# lcmeter.net
KiCad netlist of a schematic drawn in EAGLE
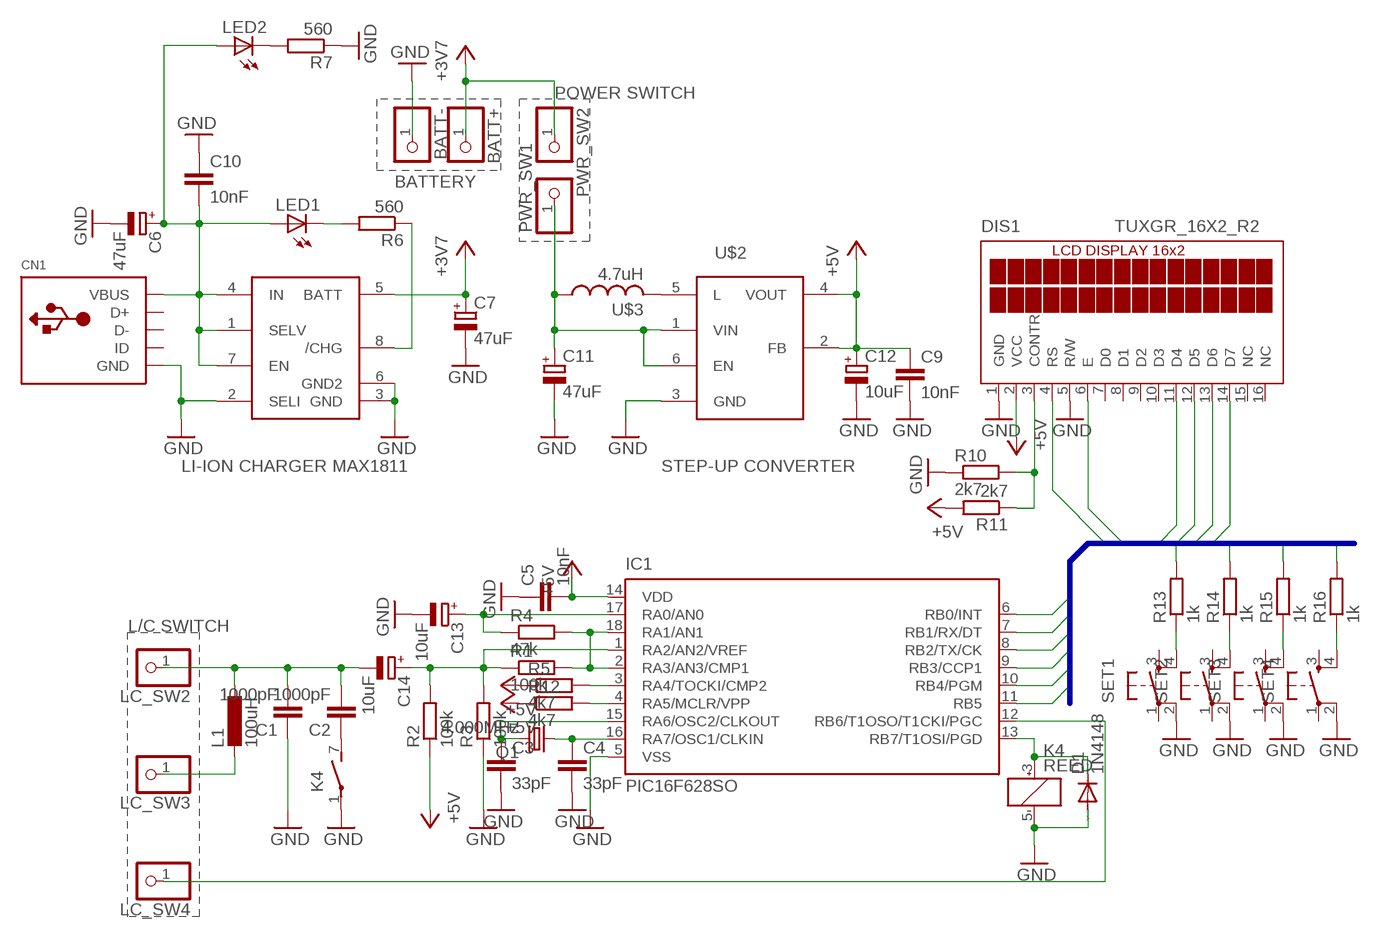
[diagram p0: schematic, sheet 1]

(export (version "E")
  (design (tool "Eeschema 10.0.6"))
  (components
    (comp (ref "BATT+")
      (value "PINHD-1X1")
      (footprint "eagle-import:1X01")
      (libsource (lib "eagle-import") (part "PINHD-1X1"))
    )
    (comp (ref "BATT-")
      (value "PINHD-1X1")
      (footprint "eagle-import:1X01")
      (libsource (lib "eagle-import") (part "PINHD-1X1"))
    )
    (comp (ref "C1")
      (value "1000pF")
      (footprint "eagle-import:C0805")
      (libsource (lib "eagle-import") (part "C-EUC0805"))
    )
    (comp (ref "C2")
      (value "1000pF")
      (footprint "eagle-import:C0805")
      (libsource (lib "eagle-import") (part "C-EUC0805"))
    )
    (comp (ref "C3")
      (value "33pF")
      (footprint "eagle-import:C0805")
      (libsource (lib "eagle-import") (part "C-EUC0805"))
    )
    (comp (ref "C4")
      (value "33pF")
      (footprint "eagle-import:C0805")
      (libsource (lib "eagle-import") (part "C-EUC0805"))
    )
    (comp (ref "C5")
      (value "10nF")
      (footprint "eagle-import:C0805")
      (libsource (lib "eagle-import") (part "C-EUC0805"))
    )
    (comp (ref "C6")
      (value "47uF")
      (footprint "eagle-import:B_3528-21W")
      (libsource (lib "eagle-import") (part "CPOL-EUB/3528-21W"))
    )
    (comp (ref "C7")
      (value "47uF")
      (footprint "eagle-import:B_3528-21W")
      (libsource (lib "eagle-import") (part "CPOL-EUB/3528-21W"))
    )
    (comp (ref "C9")
      (value "10nF")
      (footprint "eagle-import:C0805")
      (libsource (lib "eagle-import") (part "C-EUC0805"))
    )
    (comp (ref "C10")
      (value "10nF")
      (footprint "eagle-import:C0805")
      (libsource (lib "eagle-import") (part "C-EUC0805"))
    )
    (comp (ref "C11")
      (value "47uF")
      (footprint "eagle-import:B_3528-21W")
      (libsource (lib "eagle-import") (part "CPOL-EUB/3528-21W"))
    )
    (comp (ref "C12")
      (value "10uF")
      (footprint "eagle-import:B_3528-21W")
      (libsource (lib "eagle-import") (part "CPOL-EUB/3528-21W"))
    )
    (comp (ref "C13")
      (value "10uF")
      (footprint "eagle-import:B_3528-21W")
      (libsource (lib "eagle-import") (part "CPOL-EUB/3528-21W"))
    )
    (comp (ref "C14")
      (value "10uF")
      (footprint "eagle-import:B_3528-21W")
      (libsource (lib "eagle-import") (part "CPOL-EUB/3528-21W"))
    )
    (comp (ref "CN1")
      (value "USBMINIB")
      (footprint "eagle-import:USB-MINIB")
      (libsource (lib "eagle-import") (part "USBMINIB"))
    )
    (comp (ref "D1")
      (value "1N4148")
      (footprint "eagle-import:MINIMELF")
      (libsource (lib "eagle-import") (part "DIODE-MINIMELF"))
    )
    (comp (ref "DIS1")
      (value "TUXGR_16X2_R2")
      (footprint "eagle-import:TUXGR_16X2_R2")
      (libsource (lib "eagle-import") (part "TUXGR_16X2_R2"))
    )
    (comp (ref "IC1")
      (value "PIC16F628SO")
      (footprint "eagle-import:SO-18W")
      (fields (field (name "MF") "MICROCHIP") (field (name "MPN") "PIC16F628-20I/SO"))
      (libsource (lib "eagle-import") (part "PIC16F62SO8"))
    )
    (comp (ref "K4")
      (value "REED")
      (footprint "eagle-import:REED")
      (libsource (lib "eagle-import") (part "REED"))
    )
    (comp (ref "L1")
      (value "100uH")
      (footprint "eagle-import:0204_5")
      (libsource (lib "eagle-import") (part "L-EU0204/5"))
    )
    (comp (ref "LC_SW2")
      (value "PINHD-1X1")
      (footprint "eagle-import:1X01")
      (libsource (lib "eagle-import") (part "PINHD-1X1"))
    )
    (comp (ref "LC_SW3")
      (value "PINHD-1X1")
      (footprint "eagle-import:1X01")
      (libsource (lib "eagle-import") (part "PINHD-1X1"))
    )
    (comp (ref "LC_SW4")
      (value "PINHD-1X1")
      (footprint "eagle-import:1X01")
      (libsource (lib "eagle-import") (part "PINHD-1X1"))
    )
    (comp (ref "LED1")
      (value "LED1206")
      (footprint "eagle-import:LED-1206")
      (libsource (lib "eagle-import") (part "LED1206"))
    )
    (comp (ref "LED2")
      (value "LED1206")
      (footprint "eagle-import:LED-1206")
      (libsource (lib "eagle-import") (part "LED1206"))
    )
    (comp (ref "PWR_SW1")
      (value "PINHD-1X1")
      (footprint "eagle-import:1X01")
      (libsource (lib "eagle-import") (part "PINHD-1X1"))
    )
    (comp (ref "PWR_SW2")
      (value "PINHD-1X1")
      (footprint "eagle-import:1X01")
      (libsource (lib "eagle-import") (part "PINHD-1X1"))
    )
    (comp (ref "Q1")
      (value "4.000MHz")
      (footprint "eagle-import:CRYSTAL_SM49")
      (libsource (lib "eagle-import") (part "CRYSTAL_CRYTALSM49"))
    )
    (comp (ref "R1")
      (value "100k")
      (footprint "eagle-import:R0603")
      (libsource (lib "eagle-import") (part "R-EU_R0603"))
    )
    (comp (ref "R2")
      (value "100k")
      (footprint "eagle-import:R0603")
      (libsource (lib "eagle-import") (part "R-EU_R0603"))
    )
    (comp (ref "R3")
      (value "100k")
      (footprint "eagle-import:R0603")
      (libsource (lib "eagle-import") (part "R-EU_R0603"))
    )
    (comp (ref "R4")
      (value "47k")
      (footprint "eagle-import:R0603")
      (libsource (lib "eagle-import") (part "R-EU_R0603"))
    )
    (comp (ref "R5")
      (value "4k7")
      (footprint "eagle-import:R0603")
      (libsource (lib "eagle-import") (part "R-EU_R0603"))
    )
    (comp (ref "R6")
      (value "560")
      (footprint "eagle-import:R0603")
      (libsource (lib "eagle-import") (part "R-EU_R0603"))
    )
    (comp (ref "R7")
      (value "560")
      (footprint "eagle-import:R0603")
      (libsource (lib "eagle-import") (part "R-EU_R0603"))
    )
    (comp (ref "R10")
      (value "2k7")
      (footprint "eagle-import:R0603")
      (libsource (lib "eagle-import") (part "R-EU_R0603"))
    )
    (comp (ref "R11")
      (value "2k7")
      (footprint "eagle-import:R0603")
      (libsource (lib "eagle-import") (part "R-EU_R0603"))
    )
    (comp (ref "R12")
      (value "4k7")
      (footprint "eagle-import:R0603")
      (libsource (lib "eagle-import") (part "R-EU_R0603"))
    )
    (comp (ref "R13")
      (value "1k")
      (footprint "eagle-import:R0603")
      (libsource (lib "eagle-import") (part "R-EU_R0603"))
    )
    (comp (ref "R14")
      (value "1k")
      (footprint "eagle-import:R0603")
      (libsource (lib "eagle-import") (part "R-EU_R0603"))
    )
    (comp (ref "R15")
      (value "1k")
      (footprint "eagle-import:R0603")
      (libsource (lib "eagle-import") (part "R-EU_R0603"))
    )
    (comp (ref "R16")
      (value "1k")
      (footprint "eagle-import:R0603")
      (libsource (lib "eagle-import") (part "R-EU_R0603"))
    )
    (comp (ref "SET1")
      (value "TAC_SWITCHPTH")
      (footprint "eagle-import:TACTILE-PTH")
      (libsource (lib "eagle-import") (part "TAC_SWITCHPTH"))
    )
    (comp (ref "SET2")
      (value "TAC_SWITCHPTH")
      (footprint "eagle-import:TACTILE-PTH")
      (libsource (lib "eagle-import") (part "TAC_SWITCHPTH"))
    )
    (comp (ref "SET3")
      (value "TAC_SWITCHPTH")
      (footprint "eagle-import:TACTILE-PTH")
      (libsource (lib "eagle-import") (part "TAC_SWITCHPTH"))
    )
    (comp (ref "SET4")
      (value "TAC_SWITCHPTH")
      (footprint "eagle-import:TACTILE-PTH")
      (libsource (lib "eagle-import") (part "TAC_SWITCHPTH"))
    )
    (comp (ref "U$1")
      (value "MAX1811SO8")
      (footprint "eagle-import:SO08")
      (libsource (lib "eagle-import") (part "MAX1811SO8"))
    )
    (comp (ref "U$2")
      (value "TPS6122XSOT-6")
      (footprint "eagle-import:SOT23-6")
      (libsource (lib "eagle-import") (part "TPS6122XSOT-6"))
    )
    (comp (ref "U$3")
      (value "4.7uH")
      (footprint "eagle-import:EPL3015")
      (libsource (lib "eagle-import") (part "EPL3015-OK"))
    )
  )
  (nets
    (net (code "1") (name "+3V7") (class "Default")
      (node (ref "BATT+") (pin "1") (pinfunction "1_1") (pintype "passive"))
      (node (ref "C7") (pin "+") (pinfunction "+_+") (pintype "passive"))
      (node (ref "PWR_SW2") (pin "1") (pinfunction "1_1") (pintype "passive"))
      (node (ref "U$1") (pin "5") (pinfunction "BATT_5") (pintype "bidirectional"))
    )
    (net (code "2") (name "+5V") (class "Default")
      (node (ref "C12") (pin "+") (pinfunction "+_+") (pintype "passive"))
      (node (ref "C5") (pin "2") (pinfunction "2_2") (pintype "passive"))
      (node (ref "C9") (pin "1") (pinfunction "1_1") (pintype "passive"))
      (node (ref "DIS1") (pin "2") (pinfunction "VCC_2") (pintype "power_in"))
      (node (ref "IC1") (pin "14") (pinfunction "VDD_14") (pintype "power_in"))
      (node (ref "R11") (pin "2") (pinfunction "2_2") (pintype "passive"))
      (node (ref "R12") (pin "1") (pinfunction "1_1") (pintype "passive"))
      (node (ref "R2") (pin "1") (pinfunction "1_1") (pintype "passive"))
      (node (ref "R5") (pin "1") (pinfunction "1_1") (pintype "passive"))
      (node (ref "U$2") (pin "2") (pinfunction "FB_2") (pintype "bidirectional"))
      (node (ref "U$2") (pin "4") (pinfunction "VOUT_4") (pintype "power_in"))
    )
    (net (code "3") (name "/LCDPIN0") (class "Default")
      (node (ref "DIS1") (pin "4") (pinfunction "RS_4") (pintype "input"))
      (node (ref "IC1") (pin "6") (pinfunction "RB0/INT_6") (pintype "bidirectional"))
    )
    (net (code "4") (name "/LCDPIN1") (class "Default")
      (node (ref "DIS1") (pin "6") (pinfunction "E_6") (pintype "input"))
      (node (ref "IC1") (pin "7") (pinfunction "RB1/RX/DT_7") (pintype "bidirectional"))
    )
    (net (code "5") (name "/LCDPIN2") (class "Default")
      (node (ref "DIS1") (pin "11") (pinfunction "D4_11") (pintype "input"))
      (node (ref "IC1") (pin "8") (pinfunction "RB2/TX/CK_8") (pintype "bidirectional"))
      (node (ref "R13") (pin "2") (pinfunction "2_2") (pintype "passive"))
    )
    (net (code "6") (name "/LCDPIN3") (class "Default")
      (node (ref "DIS1") (pin "12") (pinfunction "D5_12") (pintype "input"))
      (node (ref "IC1") (pin "9") (pinfunction "RB3/CCP1_9") (pintype "bidirectional"))
      (node (ref "R14") (pin "2") (pinfunction "2_2") (pintype "passive"))
    )
    (net (code "7") (name "/LCDPIN4") (class "Default")
      (node (ref "DIS1") (pin "13") (pinfunction "D6_13") (pintype "input"))
      (node (ref "IC1") (pin "11") (pinfunction "RB5_11") (pintype "bidirectional"))
      (node (ref "R15") (pin "2") (pinfunction "2_2") (pintype "passive"))
    )
    (net (code "8") (name "/LCDPIN5") (class "Default")
      (node (ref "DIS1") (pin "14") (pinfunction "D7_14") (pintype "input"))
      (node (ref "IC1") (pin "10") (pinfunction "RB4/PGM_10") (pintype "bidirectional"))
      (node (ref "R16") (pin "2") (pinfunction "2_2") (pintype "passive"))
    )
    (net (code "9") (name "GND") (class "Default")
      (node (ref "BATT-") (pin "1") (pinfunction "1_1") (pintype "passive"))
      (node (ref "C1") (pin "1") (pinfunction "1_1") (pintype "passive"))
      (node (ref "C10") (pin "1") (pinfunction "1_1") (pintype "passive"))
      (node (ref "C11") (pin "-") (pinfunction "-_-") (pintype "passive"))
      (node (ref "C12") (pin "-") (pinfunction "-_-") (pintype "passive"))
      (node (ref "C13") (pin "-") (pinfunction "-_-") (pintype "passive"))
      (node (ref "C3") (pin "2") (pinfunction "2_2") (pintype "passive"))
      (node (ref "C4") (pin "2") (pinfunction "2_2") (pintype "passive"))
      (node (ref "C5") (pin "1") (pinfunction "1_1") (pintype "passive"))
      (node (ref "C6") (pin "-") (pinfunction "-_-") (pintype "passive"))
      (node (ref "C7") (pin "-") (pinfunction "-_-") (pintype "passive"))
      (node (ref "C9") (pin "2") (pinfunction "2_2") (pintype "passive"))
      (node (ref "CN1") (pin "GND") (pinfunction "GND_GND") (pintype "power_in"))
      (node (ref "D1") (pin "A") (pinfunction "A_A") (pintype "passive"))
      (node (ref "DIS1") (pin "1") (pinfunction "GND_1") (pintype "power_in"))
      (node (ref "DIS1") (pin "5") (pinfunction "R/W_5") (pintype "input"))
      (node (ref "IC1") (pin "5") (pinfunction "VSS_5") (pintype "power_in"))
      (node (ref "K4") (pin "1") (pinfunction "P_1") (pintype "passive"))
      (node (ref "K4") (pin "5") (pinfunction "-_5") (pintype "passive"))
      (node (ref "R10") (pin "1") (pinfunction "1_1") (pintype "passive"))
      (node (ref "R3") (pin "1") (pinfunction "1_1") (pintype "passive"))
      (node (ref "R7") (pin "1") (pinfunction "1_1") (pintype "passive"))
      (node (ref "SET1") (pin "2") (pinfunction "2_2") (pintype "passive"))
      (node (ref "SET2") (pin "2") (pinfunction "2_2") (pintype "passive"))
      (node (ref "SET3") (pin "2") (pinfunction "2_2") (pintype "passive"))
      (node (ref "SET4") (pin "2") (pinfunction "2_2") (pintype "passive"))
      (node (ref "U$1") (pin "2") (pinfunction "SELI_2") (pintype "bidirectional"))
      (node (ref "U$1") (pin "3") (pinfunction "GND_3") (pintype "bidirectional"))
      (node (ref "U$1") (pin "6") (pinfunction "GND2_6") (pintype "bidirectional"))
      (node (ref "U$2") (pin "3") (pinfunction "GND_3") (pintype "power_in"))
    )
    (net (code "10") (name "Net-(C1-Pad2)") (class "Default")
      (node (ref "C1") (pin "2") (pinfunction "2_2") (pintype "passive"))
      (node (ref "C14") (pin "-") (pinfunction "-_-") (pintype "passive"))
      (node (ref "C2") (pin "2") (pinfunction "2_2") (pintype "passive"))
      (node (ref "L1") (pin "1") (pinfunction "1_1") (pintype "passive"))
      (node (ref "LC_SW2") (pin "1") (pinfunction "1_1") (pintype "passive"))
    )
    (net (code "11") (name "Net-(DIS1-CONTR)") (class "Default")
      (node (ref "DIS1") (pin "3") (pinfunction "CONTR_3") (pintype "input"))
      (node (ref "R10") (pin "2") (pinfunction "2_2") (pintype "passive"))
      (node (ref "R11") (pin "1") (pinfunction "1_1") (pintype "passive"))
    )
    (net (code "12") (name "Net-(IC1-RA0{slash}AN0)") (class "Default")
      (node (ref "C13") (pin "+") (pinfunction "+_+") (pintype "passive"))
      (node (ref "IC1") (pin "17") (pinfunction "RA0/AN0_17") (pintype "bidirectional"))
      (node (ref "R4") (pin "1") (pinfunction "1_1") (pintype "passive"))
    )
    (net (code "13") (name "Net-(IC1-RA1{slash}AN1)") (class "Default")
      (node (ref "IC1") (pin "18") (pinfunction "RA1/AN1_18") (pintype "bidirectional"))
      (node (ref "IC1") (pin "2") (pinfunction "RA3/AN3/CMP1_2") (pintype "bidirectional"))
      (node (ref "R1") (pin "2") (pinfunction "2_2") (pintype "passive"))
      (node (ref "R4") (pin "2") (pinfunction "2_2") (pintype "passive"))
    )
    (net (code "14") (name "Net-(IC1-RA2{slash}AN2{slash}VREF)") (class "Default")
      (node (ref "C14") (pin "+") (pinfunction "+_+") (pintype "passive"))
      (node (ref "IC1") (pin "1") (pinfunction "RA2/AN2/VREF_1") (pintype "bidirectional"))
      (node (ref "R1") (pin "1") (pinfunction "1_1") (pintype "passive"))
      (node (ref "R2") (pin "2") (pinfunction "2_2") (pintype "passive"))
      (node (ref "R3") (pin "2") (pinfunction "2_2") (pintype "passive"))
    )
    (net (code "15") (name "Net-(IC1-RA4{slash}TOCKI{slash}CMP2)") (class "Default")
      (node (ref "IC1") (pin "3") (pinfunction "RA4/TOCKI/CMP2_3") (pintype "bidirectional"))
      (node (ref "R5") (pin "2") (pinfunction "2_2") (pintype "passive"))
    )
    (net (code "16") (name "Net-(IC1-RA5{slash}MCLR{slash}VPP)") (class "Default")
      (node (ref "IC1") (pin "4") (pinfunction "RA5/MCLR/VPP_4") (pintype "bidirectional"))
      (node (ref "R12") (pin "2") (pinfunction "2_2") (pintype "passive"))
    )
    (net (code "17") (name "Net-(IC1-RA6{slash}OSC2{slash}CLKOUT)") (class "Default")
      (node (ref "C3") (pin "1") (pinfunction "1_1") (pintype "passive"))
      (node (ref "IC1") (pin "15") (pinfunction "RA6/OSC2/CLKOUT_15") (pintype "bidirectional"))
      (node (ref "Q1") (pin "2") (pinfunction "2_2") (pintype "passive"))
    )
    (net (code "18") (name "Net-(IC1-RA7{slash}OSC1{slash}CLKIN)") (class "Default")
      (node (ref "C4") (pin "1") (pinfunction "1_1") (pintype "passive"))
      (node (ref "IC1") (pin "16") (pinfunction "RA7/OSC1/CLKIN_16") (pintype "bidirectional"))
      (node (ref "Q1") (pin "1") (pinfunction "1_1") (pintype "passive"))
    )
    (net (code "19") (name "Net-(IC1-RB6{slash}T1OSO{slash}T1CKI{slash}PGC)") (class "Default")
      (node (ref "IC1") (pin "12") (pinfunction "RB6/T1OSO/T1CKI/PGC_12") (pintype "bidirectional"))
      (node (ref "LC_SW4") (pin "1") (pinfunction "1_1") (pintype "passive"))
    )
    (net (code "20") (name "Net-(IC1-RB7{slash}T1OSI{slash}PGD)") (class "Default")
      (node (ref "D1") (pin "C") (pinfunction "C_C") (pintype "passive"))
      (node (ref "IC1") (pin "13") (pinfunction "RB7/T1OSI/PGD_13") (pintype "bidirectional"))
      (node (ref "K4") (pin "3") (pinfunction "+_3") (pintype "passive"))
    )
    (net (code "21") (name "Net-(K4B-S)") (class "Default")
      (node (ref "C2") (pin "1") (pinfunction "1_1") (pintype "passive"))
      (node (ref "K4") (pin "7") (pinfunction "S_7") (pintype "passive"))
    )
    (net (code "22") (name "Net-(L1-Pad2)") (class "Default")
      (node (ref "L1") (pin "2") (pinfunction "2_2") (pintype "passive"))
      (node (ref "LC_SW3") (pin "1") (pinfunction "1_1") (pintype "passive"))
    )
    (net (code "23") (name "Net-(LED1-PadC)") (class "Default")
      (node (ref "LED1") (pin "C") (pinfunction "C_C") (pintype "passive"))
      (node (ref "R6") (pin "2") (pinfunction "2_2") (pintype "passive"))
    )
    (net (code "24") (name "Net-(LED2-PadC)") (class "Default")
      (node (ref "LED2") (pin "C") (pinfunction "C_C") (pintype "passive"))
      (node (ref "R7") (pin "2") (pinfunction "2_2") (pintype "passive"))
    )
    (net (code "25") (name "Net-(R13-Pad1)") (class "Default")
      (node (ref "R13") (pin "1") (pinfunction "1_1") (pintype "passive"))
      (node (ref "SET1") (pin "4") (pinfunction "4_4") (pintype "passive"))
    )
    (net (code "26") (name "Net-(R14-Pad1)") (class "Default")
      (node (ref "R14") (pin "1") (pinfunction "1_1") (pintype "passive"))
      (node (ref "SET2") (pin "4") (pinfunction "4_4") (pintype "passive"))
    )
    (net (code "27") (name "Net-(R15-Pad1)") (class "Default")
      (node (ref "R15") (pin "1") (pinfunction "1_1") (pintype "passive"))
      (node (ref "SET3") (pin "4") (pinfunction "4_4") (pintype "passive"))
    )
    (net (code "28") (name "Net-(R16-Pad1)") (class "Default")
      (node (ref "R16") (pin "1") (pinfunction "1_1") (pintype "passive"))
      (node (ref "SET4") (pin "4") (pinfunction "4_4") (pintype "passive"))
    )
    (net (code "29") (name "Net-(U$1-EN)") (class "Default")
      (node (ref "C10") (pin "2") (pinfunction "2_2") (pintype "passive"))
      (node (ref "C6") (pin "+") (pinfunction "+_+") (pintype "passive"))
      (node (ref "CN1") (pin "VBUS") (pinfunction "VBUS_VBUS") (pintype "power_in"))
      (node (ref "LED1") (pin "A") (pinfunction "A_A") (pintype "passive"))
      (node (ref "LED2") (pin "A") (pinfunction "A_A") (pintype "passive"))
      (node (ref "U$1") (pin "1") (pinfunction "SELV_1") (pintype "bidirectional"))
      (node (ref "U$1") (pin "4") (pinfunction "IN_4") (pintype "bidirectional"))
      (node (ref "U$1") (pin "7") (pinfunction "EN_7") (pintype "bidirectional"))
    )
    (net (code "30") (name "Net-(U$1-{slash}CHG)") (class "Default")
      (node (ref "R6") (pin "1") (pinfunction "1_1") (pintype "passive"))
      (node (ref "U$1") (pin "8") (pinfunction "/CHG_8") (pintype "bidirectional"))
    )
    (net (code "31") (name "Net-(U$2-EN)") (class "Default")
      (node (ref "C11") (pin "+") (pinfunction "+_+") (pintype "passive"))
      (node (ref "PWR_SW1") (pin "1") (pinfunction "1_1") (pintype "passive"))
      (node (ref "U$2") (pin "1") (pinfunction "VIN_1") (pintype "power_in"))
      (node (ref "U$2") (pin "6") (pinfunction "EN_6") (pintype "bidirectional"))
      (node (ref "U$3") (pin "P$1") (pinfunction "1_P$1") (pintype "passive"))
    )
    (net (code "32") (name "Net-(U$2-L)") (class "Default")
      (node (ref "U$2") (pin "5") (pinfunction "L_5") (pintype "bidirectional"))
      (node (ref "U$3") (pin "P$2") (pinfunction "2_P$2") (pintype "passive"))
    )
    (net (code "33") (name "unconnected-(CN1-PadD+)") (class "Default")
      (node (ref "CN1") (pin "D+") (pinfunction "D+_D+") (pintype "bidirectional"))
    )
    (net (code "34") (name "unconnected-(CN1-PadD-)") (class "Default")
      (node (ref "CN1") (pin "D-") (pinfunction "D-_D-") (pintype "bidirectional"))
    )
    (net (code "35") (name "unconnected-(CN1-PadID)") (class "Default")
      (node (ref "CN1") (pin "ID") (pinfunction "ID_ID") (pintype "bidirectional"))
    )
    (net (code "36") (name "unconnected-(DIS1-D0-Pad7)") (class "Default")
      (node (ref "DIS1") (pin "7") (pinfunction "D0_7") (pintype "input"))
    )
    (net (code "37") (name "unconnected-(DIS1-D1-Pad8)") (class "Default")
      (node (ref "DIS1") (pin "8") (pinfunction "D1_8") (pintype "input"))
    )
    (net (code "38") (name "unconnected-(DIS1-D2-Pad9)") (class "Default")
      (node (ref "DIS1") (pin "9") (pinfunction "D2_9") (pintype "input"))
    )
    (net (code "39") (name "unconnected-(DIS1-D3-Pad10)") (class "Default")
      (node (ref "DIS1") (pin "10") (pinfunction "D3_10") (pintype "input"))
    )
    (net (code "40") (name "unconnected-(DIS1-NC-Pad15)") (class "Default")
      (node (ref "DIS1") (pin "15") (pinfunction "NC_15") (pintype "no_connect"))
    )
    (net (code "41") (name "unconnected-(DIS1-NC-Pad16)") (class "Default")
      (node (ref "DIS1") (pin "16") (pinfunction "NC_16") (pintype "no_connect"))
    )
    (net (code "42") (name "unconnected-(SET1-Pad1)") (class "Default")
      (node (ref "SET1") (pin "1") (pinfunction "1_1") (pintype "passive"))
    )
    (net (code "43") (name "unconnected-(SET1-Pad3)") (class "Default")
      (node (ref "SET1") (pin "3") (pinfunction "3_3") (pintype "passive"))
    )
    (net (code "44") (name "unconnected-(SET2-Pad1)") (class "Default")
      (node (ref "SET2") (pin "1") (pinfunction "1_1") (pintype "passive"))
    )
    (net (code "45") (name "unconnected-(SET2-Pad3)") (class "Default")
      (node (ref "SET2") (pin "3") (pinfunction "3_3") (pintype "passive"))
    )
    (net (code "46") (name "unconnected-(SET3-Pad1)") (class "Default")
      (node (ref "SET3") (pin "1") (pinfunction "1_1") (pintype "passive"))
    )
    (net (code "47") (name "unconnected-(SET3-Pad3)") (class "Default")
      (node (ref "SET3") (pin "3") (pinfunction "3_3") (pintype "passive"))
    )
    (net (code "48") (name "unconnected-(SET4-Pad1)") (class "Default")
      (node (ref "SET4") (pin "1") (pinfunction "1_1") (pintype "passive"))
    )
    (net (code "49") (name "unconnected-(SET4-Pad3)") (class "Default")
      (node (ref "SET4") (pin "3") (pinfunction "3_3") (pintype "passive"))
    )
  )
)
